# Power_Supply.net
KiCad netlist of a schematic drawn in Altium Designer
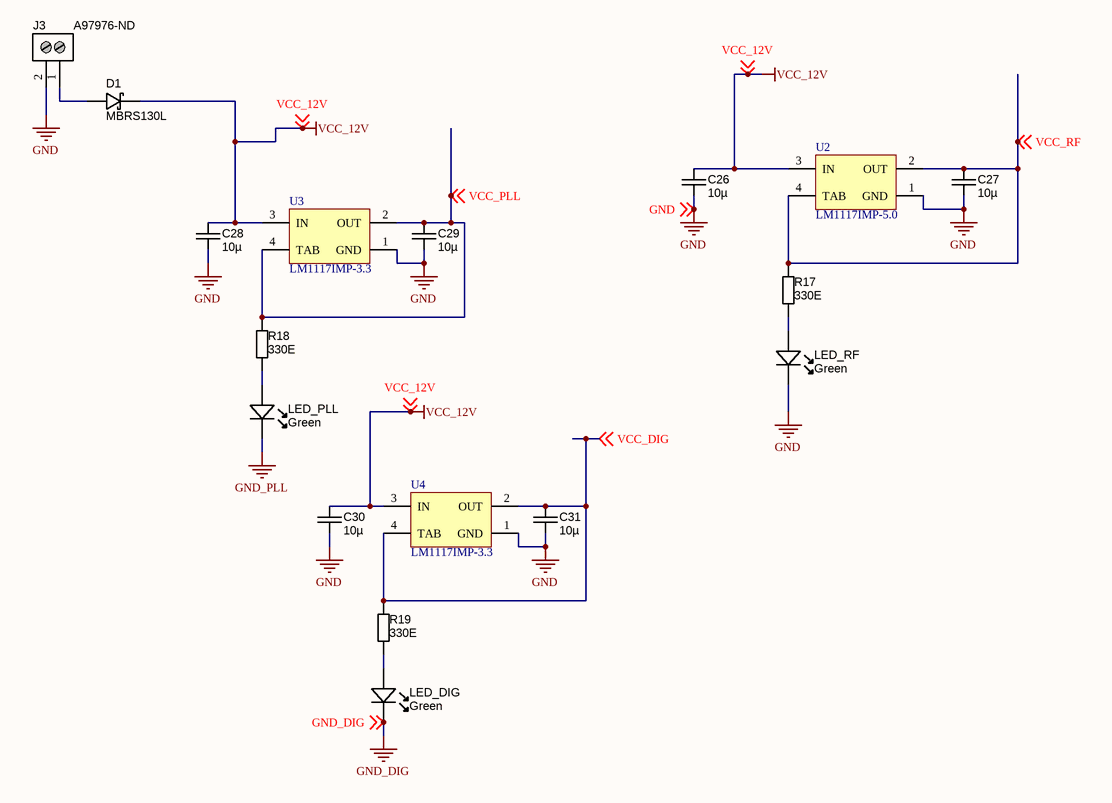
[diagram p0: Power_Supply.SchDoc]

(export (version "E")
  (design (tool "Eeschema 10.0.6"))
  (components
    (comp (ref "C26")
      (value "10µ")
      (footprint "CAPC3216X180N")
      (description "Capacitor SMD Cer 10uF 10% 16V X7R 1206")
      (fields (field (name "TOLERANCE") "±10%") (field (name "Comment") "approved sub OK"))
      (libsource (lib "PBL - Capacitors") (part "CAPC_10u_1206_16V"))
    )
    (comp (ref "C27")
      (value "10µ")
      (footprint "CAPC3216X180N")
      (description "Capacitor SMD Cer 10uF 10% 16V X7R 1206")
      (fields (field (name "TOLERANCE") "±10%") (field (name "Comment") "approved sub OK"))
      (libsource (lib "PBL - Capacitors") (part "CAPC_10u_1206_16V"))
    )
    (comp (ref "C28")
      (value "10µ")
      (footprint "CAPC3216X180N")
      (description "Capacitor SMD Cer 10uF 10% 16V X7R 1206")
      (fields (field (name "TOLERANCE") "±10%") (field (name "Comment") "approved sub OK"))
      (libsource (lib "PBL - Capacitors") (part "CAPC_10u_1206_16V"))
    )
    (comp (ref "C29")
      (value "10µ")
      (footprint "CAPC3216X180N")
      (description "Capacitor SMD Cer 10uF 10% 16V X7R 1206")
      (fields (field (name "TOLERANCE") "±10%") (field (name "Comment") "approved sub OK"))
      (libsource (lib "PBL - Capacitors") (part "CAPC_10u_1206_16V"))
    )
    (comp (ref "C30")
      (value "10µ")
      (footprint "CAPC3216X180N")
      (description "Capacitor SMD Cer 10uF 10% 16V X7R 1206")
      (fields (field (name "TOLERANCE") "±10%") (field (name "Comment") "approved sub OK"))
      (libsource (lib "PBL - Capacitors") (part "CAPC_10u_1206_16V"))
    )
    (comp (ref "C31")
      (value "10µ")
      (footprint "CAPC3216X180N")
      (description "Capacitor SMD Cer 10uF 10% 16V X7R 1206")
      (fields (field (name "TOLERANCE") "±10%") (field (name "Comment") "approved sub OK"))
      (libsource (lib "PBL - Capacitors") (part "CAPC_10u_1206_16V"))
    )
    (comp (ref "D1")
      (value "MBRS130L")
      (footprint "DO-214AA")
      (description "Diode Schottky SMD 30V 2A DO-214AA")
      (libsource (lib "PBL - Diodes") (part "DIODE_SCHOTTKY_MBRS130L"))
    )
    (comp (ref "J3")
      (value "Stackable ScrewTerm")
      (footprint "2P_PCB_ScrewTerm_90S_3.81MM")
      (description "Terminal Block Screw Type THT 2-Position 3.81mm pitch")
      (fields (field (name "SUPPLIER PART NUMBER 1") "A97976-ND"))
      (libsource (lib "PBL - Connectors") (part "2P_ScrewTerm_90S_3.81MM"))
    )
    (comp (ref "LED_DIG")
      (value "Green")
      (footprint "LED-0603-GREEN")
      (description "LED 0603 SMD Green 570nm 50mcd 20mA")
      (libsource (lib "PBL - Light Sources") (part "LED_SMD_Green_0603_570nm"))
    )
    (comp (ref "LED_PLL")
      (value "Green")
      (footprint "LED-0603-GREEN")
      (description "LED 0603 SMD Green 570nm 50mcd 20mA")
      (libsource (lib "PBL - Light Sources") (part "LED_SMD_Green_0603_570nm"))
    )
    (comp (ref "LED_RF")
      (value "Green")
      (footprint "LED-0603-GREEN")
      (description "LED 0603 SMD Green 570nm 50mcd 20mA")
      (libsource (lib "PBL - Light Sources") (part "LED_SMD_Green_0603_570nm"))
    )
    (comp (ref "R17")
      (value "330E")
      (footprint "RESC1608X55N")
      (description "Resistor SMD chip 1.5k Ohm 0.1W 5% 0603")
      (fields (field (name "TOLERANCE") "±5%") (field (name "Comment") "Thick Film"))
      (libsource (lib "PBL - Resistors") (part "RES_1K5_0603_5%"))
    )
    (comp (ref "R18")
      (value "330E")
      (footprint "RESC1608X55N")
      (description "Resistor SMD chip 1.5k Ohm 0.1W 5% 0603")
      (fields (field (name "TOLERANCE") "±5%") (field (name "Comment") "Thick Film"))
      (libsource (lib "PBL - Resistors") (part "RES_1K5_0603_5%"))
    )
    (comp (ref "R19")
      (value "330E")
      (footprint "RESC1608X55N")
      (description "Resistor SMD chip 1.5k Ohm 0.1W 5% 0603")
      (fields (field (name "TOLERANCE") "±5%") (field (name "Comment") "Thick Film"))
      (libsource (lib "PBL - Resistors") (part "RES_1K5_0603_5%"))
    )
    (comp (ref "U2")
      (value "LM1117IMP-5.0")
      (footprint "SOT223_L")
      (description "800mA Low-Dropout Linear Regulator, 4-pin SOT-223")
      (fields
        (field (name "MANUFACTURER") "National Semiconductor")
        (field (name "PUBLISHER") "Altium Limited")
      )
      (libsource (lib "NSC LDO") (part "LM1117IMP-5.0"))
    )
    (comp (ref "U3")
      (value "LM1117IMP-3.3")
      (footprint "SOT223_L")
      (description "800mA Low-Dropout Linear Regulator, 4-pin SOT-223")
      (fields
        (field (name "MANUFACTURER") "National Semiconductor")
        (field (name "PUBLISHER") "Altium Limited")
      )
      (libsource (lib "NSC LDO") (part "LM1117IMP-3.3"))
    )
    (comp (ref "U4")
      (value "LM1117IMP-3.3")
      (footprint "SOT223_L")
      (description "800mA Low-Dropout Linear Regulator, 4-pin SOT-223")
      (fields
        (field (name "MANUFACTURER") "National Semiconductor")
        (field (name "PUBLISHER") "Altium Limited")
      )
      (libsource (lib "NSC LDO") (part "LM1117IMP-3.3"))
    )
  )
  (nets
    (net (code "1") (name "GND") (class "Default")
      (node (ref "C26") (pin "2") (pintype "passive"))
      (node (ref "C27") (pin "2") (pintype "passive"))
      (node (ref "C28") (pin "2") (pintype "passive"))
      (node (ref "C29") (pin "2") (pintype "passive"))
      (node (ref "C30") (pin "2") (pintype "passive"))
      (node (ref "C31") (pin "2") (pintype "passive"))
      (node (ref "J3") (pin "2") (pinfunction "2_2") (pintype "passive"))
      (node (ref "LED_RF") (pin "K") (pinfunction "K_K") (pintype "passive"))
      (node (ref "U2") (pin "1") (pinfunction "GND_1") (pintype "power_in"))
      (node (ref "U3") (pin "1") (pinfunction "GND_1") (pintype "power_in"))
      (node (ref "U4") (pin "1") (pinfunction "GND_1") (pintype "power_in"))
    )
    (net (code "2") (name "GND_DIG") (class "Default")
      (node (ref "LED_DIG") (pin "K") (pinfunction "K_K") (pintype "passive"))
    )
    (net (code "3") (name "GND_PLL") (class "Default")
      (node (ref "LED_PLL") (pin "K") (pinfunction "K_K") (pintype "passive"))
    )
    (net (code "4") (name "Net-(D1-PadA)") (class "Default")
      (node (ref "D1") (pin "A") (pinfunction "A_A") (pintype "passive"))
      (node (ref "J3") (pin "1") (pinfunction "1_1") (pintype "passive"))
    )
    (net (code "5") (name "Net-(LED_DIG-PadA)") (class "Default")
      (node (ref "LED_DIG") (pin "A") (pinfunction "A_A") (pintype "passive"))
      (node (ref "R19") (pin "2") (pinfunction "2_2") (pintype "passive"))
    )
    (net (code "6") (name "Net-(LED_PLL-PadA)") (class "Default")
      (node (ref "LED_PLL") (pin "A") (pinfunction "A_A") (pintype "passive"))
      (node (ref "R18") (pin "2") (pinfunction "2_2") (pintype "passive"))
    )
    (net (code "7") (name "Net-(LED_RF-PadA)") (class "Default")
      (node (ref "LED_RF") (pin "A") (pinfunction "A_A") (pintype "passive"))
      (node (ref "R17") (pin "2") (pinfunction "2_2") (pintype "passive"))
    )
    (net (code "8") (name "VCC_12V") (class "Default")
      (node (ref "C26") (pin "1") (pintype "passive"))
      (node (ref "C28") (pin "1") (pintype "passive"))
      (node (ref "C30") (pin "1") (pintype "passive"))
      (node (ref "D1") (pin "K") (pinfunction "K_K") (pintype "passive"))
      (node (ref "U2") (pin "3") (pinfunction "IN_3") (pintype "power_in"))
      (node (ref "U3") (pin "3") (pinfunction "IN_3") (pintype "power_in"))
      (node (ref "U4") (pin "3") (pinfunction "IN_3") (pintype "power_in"))
    )
    (net (code "9") (name "VCC_DIG") (class "Default")
      (node (ref "C31") (pin "1") (pintype "passive"))
      (node (ref "R19") (pin "1") (pinfunction "1_1") (pintype "passive"))
      (node (ref "U4") (pin "2") (pinfunction "OUT_2") (pintype "power_in"))
      (node (ref "U4") (pin "4") (pinfunction "TAB_4") (pintype "power_in"))
    )
    (net (code "10") (name "VCC_PLL") (class "Default")
      (node (ref "C29") (pin "1") (pintype "passive"))
      (node (ref "R18") (pin "1") (pinfunction "1_1") (pintype "passive"))
      (node (ref "U3") (pin "2") (pinfunction "OUT_2") (pintype "power_in"))
      (node (ref "U3") (pin "4") (pinfunction "TAB_4") (pintype "power_in"))
    )
    (net (code "11") (name "VCC_RF") (class "Default")
      (node (ref "C27") (pin "1") (pintype "passive"))
      (node (ref "R17") (pin "1") (pinfunction "1_1") (pintype "passive"))
      (node (ref "U2") (pin "2") (pinfunction "OUT_2") (pintype "power_in"))
      (node (ref "U2") (pin "4") (pinfunction "TAB_4") (pintype "power_in"))
    )
  )
)
